# Pointcast_upper_board_V1_03.net
KiCad netlist of a schematic drawn in EAGLE
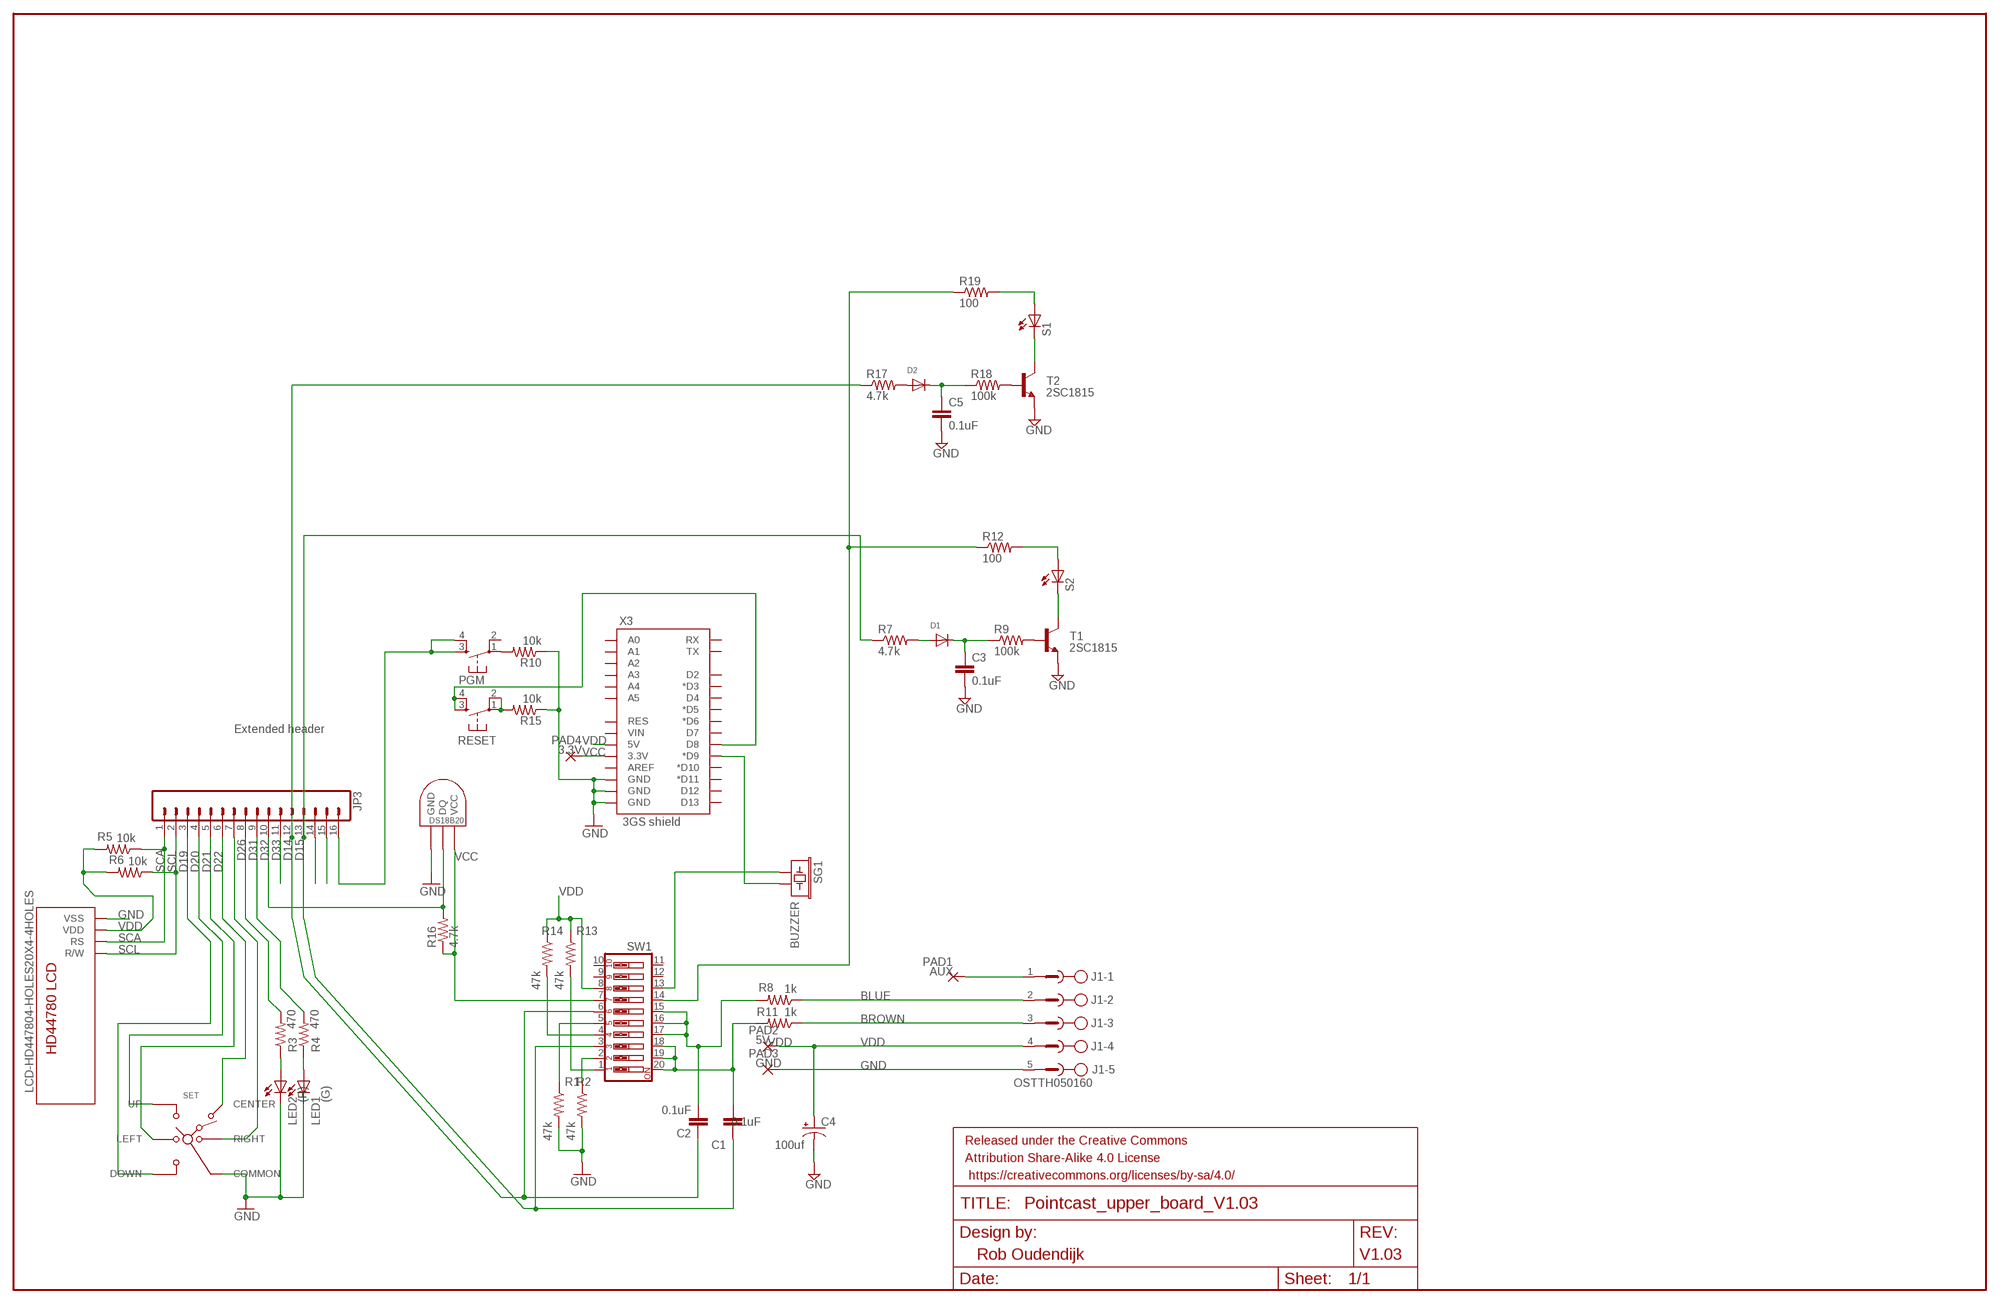
[diagram p0: schematic, sheet 1]

(export (version "E")
  (design (tool "Eeschema 10.0.6"))
  (components
    (comp (ref "C1")
      (value "0.1uF")
      (footprint "eagle-import:C025-024X044")
      (libsource (lib "eagle-import") (part "C-EU025-024X044"))
    )
    (comp (ref "C2")
      (value "0.1uF")
      (footprint "eagle-import:C025-024X044")
      (libsource (lib "eagle-import") (part "C-EU025-024X044"))
    )
    (comp (ref "C3")
      (value "0.1uF")
      (footprint "eagle-import:C025-024X044")
      (libsource (lib "eagle-import") (part "C-EU025-024X044"))
    )
    (comp (ref "C4")
      (value "100uf")
      (footprint "eagle-import:CPOL-RADIAL-100UF-25V")
      (libsource (lib "eagle-import") (part "CAP_POLPTH1"))
    )
    (comp (ref "C5")
      (value "0.1uF")
      (footprint "eagle-import:C025-024X044")
      (libsource (lib "eagle-import") (part "C-EU025-024X044"))
    )
    (comp (ref "D1")
      (value "DIODEDIODE_BIG")
      (footprint "eagle-import:DO41-10")
      (libsource (lib "eagle-import") (part "DIODEDIODE_BIG"))
    )
    (comp (ref "D2")
      (value "DIODEDIODE_BIG")
      (footprint "eagle-import:DO41-10")
      (libsource (lib "eagle-import") (part "DIODEDIODE_BIG"))
    )
    (comp (ref "FRAME1")
      (value "FRAME-LEDGER")
      (footprint "eagle-import:CREATIVE_COMMONS")
      (libsource (lib "eagle-import") (part "FRAME-LEDGER"))
    )
    (comp (ref "J1")
      (value "OSTTH050160")
      (footprint "eagle-import:EDSTL130-05")
      (libsource (lib "eagle-import") (part "OSTTH050160"))
    )
    (comp (ref "JP3")
      (value "Extended header")
      (footprint "eagle-import:1X16")
      (libsource (lib "eagle-import") (part "M16PTH"))
    )
    (comp (ref "LED1")
      (value "(G)")
      (footprint "eagle-import:LED3MM")
      (libsource (lib "eagle-import") (part "LED3MM"))
    )
    (comp (ref "LED2")
      (value "(R)")
      (footprint "eagle-import:LED3MM")
      (libsource (lib "eagle-import") (part "LED3MM"))
    )
    (comp (ref "PAD1")
      (value "AUX")
      (footprint "eagle-import:2,15_1,0")
      (libsource (lib "eagle-import") (part "2,15/1,0"))
    )
    (comp (ref "PAD2")
      (value "5V")
      (footprint "eagle-import:2,15_1,0")
      (libsource (lib "eagle-import") (part "2,15/1,0"))
    )
    (comp (ref "PAD3")
      (value "GND")
      (footprint "eagle-import:2,15_1,0")
      (libsource (lib "eagle-import") (part "2,15/1,0"))
    )
    (comp (ref "PAD4")
      (value "3.3V")
      (footprint "eagle-import:2,15_1,0")
      (libsource (lib "eagle-import") (part "2,15/1,0"))
    )
    (comp (ref "PGM")
      (value "DTS-6")
      (footprint "eagle-import:DTS-6")
      (libsource (lib "eagle-import") (part "DTS-6"))
    )
    (comp (ref "R1")
      (value "47k")
      (footprint "eagle-import:0207_10")
      (libsource (lib "eagle-import") (part "resistor_R-US_0207/10"))
    )
    (comp (ref "R2")
      (value "47k")
      (footprint "eagle-import:0207_10")
      (libsource (lib "eagle-import") (part "resistor_R-US_0207/10"))
    )
    (comp (ref "R3")
      (value "470")
      (footprint "eagle-import:0207_10")
      (libsource (lib "eagle-import") (part "resistor_R-US_0207/10"))
    )
    (comp (ref "R4")
      (value "470")
      (footprint "eagle-import:0207_10")
      (libsource (lib "eagle-import") (part "resistor_R-US_0207/10"))
    )
    (comp (ref "R5")
      (value "10k")
      (footprint "eagle-import:0207_10")
      (libsource (lib "eagle-import") (part "R-US_0207/10"))
    )
    (comp (ref "R6")
      (value "10k")
      (footprint "eagle-import:0207_10")
      (libsource (lib "eagle-import") (part "R-US_0207/10"))
    )
    (comp (ref "R7")
      (value "4.7k")
      (footprint "eagle-import:0207_10")
      (libsource (lib "eagle-import") (part "rcl_R-US_0207/10"))
    )
    (comp (ref "R8")
      (value "1k")
      (footprint "eagle-import:0207_10")
      (libsource (lib "eagle-import") (part "resistor_R-US_0207/10"))
    )
    (comp (ref "R9")
      (value "100k")
      (footprint "eagle-import:0207_10")
      (libsource (lib "eagle-import") (part "rcl_R-US_0207/10"))
    )
    (comp (ref "R10")
      (value "10k")
      (footprint "eagle-import:0207_10")
      (libsource (lib "eagle-import") (part "resistor_R-US_0207/10"))
    )
    (comp (ref "R11")
      (value "1k")
      (footprint "eagle-import:0207_10")
      (libsource (lib "eagle-import") (part "resistor_R-US_0207/10"))
    )
    (comp (ref "R12")
      (value "100")
      (footprint "eagle-import:0207_10")
      (libsource (lib "eagle-import") (part "rcl_R-US_0207/10"))
    )
    (comp (ref "R13")
      (value "47k")
      (footprint "eagle-import:0207_10")
      (libsource (lib "eagle-import") (part "resistor_R-US_0207/10"))
    )
    (comp (ref "R14")
      (value "47k")
      (footprint "eagle-import:0207_10")
      (libsource (lib "eagle-import") (part "resistor_R-US_0207/10"))
    )
    (comp (ref "R15")
      (value "10k")
      (footprint "eagle-import:0207_10")
      (libsource (lib "eagle-import") (part "resistor_R-US_0207/10"))
    )
    (comp (ref "R16")
      (value "4.7k")
      (footprint "eagle-import:0207_10")
      (libsource (lib "eagle-import") (part "resistor_R-US_0207/10"))
    )
    (comp (ref "R17")
      (value "4.7k")
      (footprint "eagle-import:0207_10")
      (libsource (lib "eagle-import") (part "rcl_R-US_0207/10"))
    )
    (comp (ref "R18")
      (value "100k")
      (footprint "eagle-import:0207_10")
      (libsource (lib "eagle-import") (part "rcl_R-US_0207/10"))
    )
    (comp (ref "R19")
      (value "100")
      (footprint "eagle-import:0207_10")
      (libsource (lib "eagle-import") (part "rcl_R-US_0207/10"))
    )
    (comp (ref "RESET")
      (value "DTS-6")
      (footprint "eagle-import:DTS-6")
      (libsource (lib "eagle-import") (part "DTS-6"))
    )
    (comp (ref "S1")
      (value "LED3MM")
      (footprint "eagle-import:LED3MM")
      (libsource (lib "eagle-import") (part "LED3MM"))
    )
    (comp (ref "S2")
      (value "LED3MM")
      (footprint "eagle-import:LED3MM")
      (libsource (lib "eagle-import") (part "LED3MM"))
    )
    (comp (ref "SET")
      (value "SKQUCAA010")
      (footprint "eagle-import:SKQU")
      (fields (field (name "MF") "ALPS"))
      (libsource (lib "eagle-import") (part "SKQUCAA010"))
    )
    (comp (ref "SG1")
      (value "BUZZER")
      (footprint "eagle-import:BUZZER-12MM")
      (libsource (lib "eagle-import") (part "BUZZERPTH"))
    )
    (comp (ref "SW1")
      (value "SW_DIP-10")
      (footprint "eagle-import:EDG-10")
      (libsource (lib "eagle-import") (part "SW_DIP-10"))
    )
    (comp (ref "T1")
      (value "2SC1815")
      (footprint "eagle-import:TO92-ECB")
      (libsource (lib "eagle-import") (part "2SC1815"))
    )
    (comp (ref "T2")
      (value "2SC1815")
      (footprint "eagle-import:TO92-ECB")
      (libsource (lib "eagle-import") (part "2SC1815"))
    )
    (comp (ref "TEMP")
      (value "AVA_DS1820TO92")
      (footprint "eagle-import:AVA_DS1820")
      (libsource (lib "eagle-import") (part "AVA_DS1820TO92"))
    )
    (comp (ref "X1")
      (value "LCD-HD447804-HOLES20X4-4HOLES")
      (footprint "eagle-import:LCD-20X4-4HOLES")
      (libsource (lib "eagle-import") (part "LCD-HD4478020X4-4HOLES4-HOLES"))
    )
    (comp (ref "X3")
      (value "3GS shield")
      (footprint "eagle-import:DUEMILANOVE_SHIELD")
      (libsource (lib "eagle-import") (part "ARDUINO_SHIELDLABEL"))
    )
  )
  (nets
    (net (code "1") (name "/BLUE") (class "Default")
      (node (ref "J1") (pin "2") (pinfunction "SK_2") (pintype "passive"))
      (node (ref "R8") (pin "1") (pinfunction "1_1") (pintype "passive"))
    )
    (net (code "2") (name "/BROWN") (class "Default")
      (node (ref "J1") (pin "3") (pinfunction "SK_3") (pintype "passive"))
      (node (ref "R11") (pin "1") (pinfunction "1_1") (pintype "passive"))
    )
    (net (code "3") (name "/D14") (class "Default")
      (node (ref "C2") (pin "1") (pinfunction "1_1") (pintype "passive"))
      (node (ref "JP3") (pin "12") (pinfunction "12_12") (pintype "passive"))
      (node (ref "R17") (pin "1") (pinfunction "1_1") (pintype "passive"))
      (node (ref "SW1") (pin "6") (pinfunction "6_6") (pintype "passive"))
    )
    (net (code "4") (name "/D15") (class "Default")
      (node (ref "C1") (pin "1") (pinfunction "1_1") (pintype "passive"))
      (node (ref "JP3") (pin "13") (pinfunction "13_13") (pintype "passive"))
      (node (ref "R7") (pin "1") (pinfunction "1_1") (pintype "passive"))
      (node (ref "SW1") (pin "3") (pinfunction "3_3") (pintype "passive"))
    )
    (net (code "5") (name "/D19") (class "Default")
      (node (ref "JP3") (pin "3") (pinfunction "3_3") (pintype "passive"))
      (node (ref "SET") (pin "DOWN") (pinfunction "DOWN_DOWN") (pintype "passive"))
    )
    (net (code "6") (name "/D20") (class "Default")
      (node (ref "JP3") (pin "4") (pinfunction "4_4") (pintype "passive"))
      (node (ref "SET") (pin "UP") (pinfunction "UP_UP") (pintype "passive"))
    )
    (net (code "7") (name "/D21") (class "Default")
      (node (ref "JP3") (pin "5") (pinfunction "5_5") (pintype "passive"))
      (node (ref "SET") (pin "LEFT") (pinfunction "LEFT_LEFT") (pintype "passive"))
    )
    (net (code "8") (name "/D22") (class "Default")
      (node (ref "JP3") (pin "6") (pinfunction "6_6") (pintype "passive"))
      (node (ref "SET") (pin "CENTER") (pinfunction "CENTER_CENTER") (pintype "passive"))
    )
    (net (code "9") (name "/D26") (class "Default")
      (node (ref "JP3") (pin "8") (pinfunction "8_8") (pintype "passive"))
      (node (ref "R3") (pin "2") (pinfunction "2_2") (pintype "passive"))
    )
    (net (code "10") (name "/D31") (class "Default")
      (node (ref "JP3") (pin "9") (pinfunction "9_9") (pintype "passive"))
      (node (ref "R4") (pin "2") (pinfunction "2_2") (pintype "passive"))
    )
    (net (code "11") (name "/D32") (class "Default")
      (node (ref "JP3") (pin "10") (pinfunction "10_10") (pintype "passive"))
      (node (ref "R16") (pin "2") (pinfunction "2_2") (pintype "passive"))
      (node (ref "TEMP") (pin "DQ") (pinfunction "DQ_DQ") (pintype "bidirectional"))
    )
    (net (code "12") (name "/D33") (class "Default")
      (node (ref "JP3") (pin "11") (pinfunction "11_11") (pintype "passive"))
    )
    (net (code "13") (name "/SCA") (class "Default")
      (node (ref "JP3") (pin "1") (pinfunction "1_1") (pintype "passive"))
      (node (ref "R5") (pin "1") (pinfunction "1_1") (pintype "passive"))
      (node (ref "X1") (pin "P$15") (pinfunction "RS_P$15") (pintype "input"))
    )
    (net (code "14") (name "/SCL") (class "Default")
      (node (ref "JP3") (pin "2") (pinfunction "2_2") (pintype "passive"))
      (node (ref "R6") (pin "1") (pinfunction "1_1") (pintype "passive"))
      (node (ref "X1") (pin "P$16") (pinfunction "R/W_P$16") (pintype "input"))
    )
    (net (code "15") (name "/VCC") (class "Default")
      (node (ref "PAD4") (pin "1") (pinfunction "P_1") (pintype "passive"))
      (node (ref "R16") (pin "1") (pinfunction "1_1") (pintype "passive"))
      (node (ref "SW1") (pin "7") (pinfunction "7_7") (pintype "passive"))
      (node (ref "TEMP") (pin "VDD") (pinfunction "VCC_VDD") (pintype "power_in"))
      (node (ref "X3") (pin "3.3V") (pinfunction "3.3V_3.3V") (pintype "bidirectional"))
    )
    (net (code "16") (name "/VDD") (class "Default")
      (node (ref "C4") (pin "2") (pinfunction "+_2") (pintype "passive"))
      (node (ref "J1") (pin "4") (pinfunction "SK_4") (pintype "passive"))
      (node (ref "PAD2") (pin "1") (pinfunction "P_1") (pintype "passive"))
      (node (ref "R13") (pin "1") (pinfunction "1_1") (pintype "passive"))
      (node (ref "R14") (pin "1") (pinfunction "1_1") (pintype "passive"))
      (node (ref "R5") (pin "2") (pinfunction "2_2") (pintype "passive"))
      (node (ref "R6") (pin "2") (pinfunction "2_2") (pintype "passive"))
      (node (ref "SW1") (pin "8") (pinfunction "8_8") (pintype "passive"))
      (node (ref "X1") (pin "P$14") (pinfunction "VDD_P$14") (pintype "power_in"))
      (node (ref "X3") (pin "5V") (pinfunction "5V_5V") (pintype "bidirectional"))
    )
    (net (code "17") (name "GND") (class "Default")
      (node (ref "C3") (pin "2") (pinfunction "2_2") (pintype "passive"))
      (node (ref "C4") (pin "1") (pinfunction "-_1") (pintype "passive"))
      (node (ref "C5") (pin "2") (pinfunction "2_2") (pintype "passive"))
      (node (ref "J1") (pin "5") (pinfunction "SK_5") (pintype "passive"))
      (node (ref "LED1") (pin "K") (pinfunction "C_K") (pintype "passive"))
      (node (ref "LED2") (pin "K") (pinfunction "C_K") (pintype "passive"))
      (node (ref "PAD3") (pin "1") (pinfunction "P_1") (pintype "passive"))
      (node (ref "R1") (pin "2") (pinfunction "2_2") (pintype "passive"))
      (node (ref "R10") (pin "1") (pinfunction "1_1") (pintype "passive"))
      (node (ref "R15") (pin "1") (pinfunction "1_1") (pintype "passive"))
      (node (ref "R2") (pin "2") (pinfunction "2_2") (pintype "passive"))
      (node (ref "SET") (pin "COMMON") (pinfunction "COMMON_COMMON") (pintype "power_in"))
      (node (ref "T1") (pin "E") (pinfunction "E_E") (pintype "passive"))
      (node (ref "T2") (pin "E") (pinfunction "E_E") (pintype "passive"))
      (node (ref "TEMP") (pin "GND") (pinfunction "GND_GND") (pintype "power_in"))
      (node (ref "X1") (pin "P$13") (pinfunction "VSS_P$13") (pintype "power_in"))
      (node (ref "X3") (pin "GND@0") (pinfunction "GND_GND@0") (pintype "bidirectional"))
      (node (ref "X3") (pin "GND@1") (pinfunction "GND_GND@1") (pintype "bidirectional"))
      (node (ref "X3") (pin "GND@2") (pinfunction "GND_GND@2") (pintype "bidirectional"))
    )
    (net (code "18") (name "Net-(C1-Pad2)") (class "Default")
      (node (ref "C1") (pin "2") (pinfunction "2_2") (pintype "passive"))
      (node (ref "R11") (pin "2") (pinfunction "2_2") (pintype "passive"))
      (node (ref "SW1") (pin "18") (pinfunction "18_18") (pintype "passive"))
      (node (ref "SW1") (pin "19") (pinfunction "19_19") (pintype "passive"))
      (node (ref "SW1") (pin "20") (pinfunction "20_20") (pintype "passive"))
    )
    (net (code "19") (name "Net-(C2-Pad2)") (class "Default")
      (node (ref "C2") (pin "2") (pinfunction "2_2") (pintype "passive"))
      (node (ref "R8") (pin "2") (pinfunction "2_2") (pintype "passive"))
      (node (ref "SW1") (pin "15") (pinfunction "15_15") (pintype "passive"))
      (node (ref "SW1") (pin "16") (pinfunction "16_16") (pintype "passive"))
      (node (ref "SW1") (pin "17") (pinfunction "17_17") (pintype "passive"))
    )
    (net (code "20") (name "Net-(C3-Pad1)") (class "Default")
      (node (ref "C3") (pin "1") (pinfunction "1_1") (pintype "passive"))
      (node (ref "D1") (pin "C") (pinfunction "C_C") (pintype "passive"))
      (node (ref "R9") (pin "1") (pinfunction "1_1") (pintype "passive"))
    )
    (net (code "21") (name "Net-(C5-Pad1)") (class "Default")
      (node (ref "C5") (pin "1") (pinfunction "1_1") (pintype "passive"))
      (node (ref "D2") (pin "C") (pinfunction "C_C") (pintype "passive"))
      (node (ref "R18") (pin "1") (pinfunction "1_1") (pintype "passive"))
    )
    (net (code "22") (name "Net-(D1-PadA)") (class "Default")
      (node (ref "D1") (pin "A") (pinfunction "A_A") (pintype "passive"))
      (node (ref "R7") (pin "2") (pinfunction "2_2") (pintype "passive"))
    )
    (net (code "23") (name "Net-(D2-PadA)") (class "Default")
      (node (ref "D2") (pin "A") (pinfunction "A_A") (pintype "passive"))
      (node (ref "R17") (pin "2") (pinfunction "2_2") (pintype "passive"))
    )
    (net (code "24") (name "Net-(J1A-SK)") (class "Default")
      (node (ref "J1") (pin "1") (pinfunction "SK_1") (pintype "passive"))
      (node (ref "PAD1") (pin "1") (pinfunction "P_1") (pintype "passive"))
    )
    (net (code "25") (name "Net-(JP3-Pad7)") (class "Default")
      (node (ref "JP3") (pin "7") (pinfunction "7_7") (pintype "passive"))
      (node (ref "SET") (pin "RIGHT") (pinfunction "RIGHT_RIGHT") (pintype "passive"))
    )
    (net (code "26") (name "Net-(JP3-Pad16)") (class "Default")
      (node (ref "JP3") (pin "16") (pinfunction "16_16") (pintype "passive"))
      (node (ref "PGM") (pin "3") (pinfunction "3_3") (pintype "passive"))
      (node (ref "PGM") (pin "4") (pinfunction "4_4") (pintype "passive"))
    )
    (net (code "27") (name "Net-(LED1-PadA)") (class "Default")
      (node (ref "LED1") (pin "A") (pinfunction "A_A") (pintype "passive"))
      (node (ref "R4") (pin "1") (pinfunction "1_1") (pintype "passive"))
    )
    (net (code "28") (name "Net-(LED2-PadA)") (class "Default")
      (node (ref "LED2") (pin "A") (pinfunction "A_A") (pintype "passive"))
      (node (ref "R3") (pin "1") (pinfunction "1_1") (pintype "passive"))
    )
    (net (code "29") (name "Net-(PGM-Pad1)") (class "Default")
      (node (ref "PGM") (pin "1") (pinfunction "1_1") (pintype "passive"))
      (node (ref "R10") (pin "2") (pinfunction "2_2") (pintype "passive"))
    )
    (net (code "30") (name "Net-(R1-Pad1)") (class "Default")
      (node (ref "R1") (pin "1") (pinfunction "1_1") (pintype "passive"))
      (node (ref "SW1") (pin "5") (pinfunction "5_5") (pintype "passive"))
    )
    (net (code "31") (name "Net-(R2-Pad1)") (class "Default")
      (node (ref "R2") (pin "1") (pinfunction "1_1") (pintype "passive"))
      (node (ref "SW1") (pin "2") (pinfunction "2_2") (pintype "passive"))
    )
    (net (code "32") (name "Net-(R9-Pad2)") (class "Default")
      (node (ref "R9") (pin "2") (pinfunction "2_2") (pintype "passive"))
      (node (ref "T1") (pin "B") (pinfunction "B_B") (pintype "passive"))
    )
    (net (code "33") (name "Net-(R12-Pad1)") (class "Default")
      (node (ref "R12") (pin "1") (pinfunction "1_1") (pintype "passive"))
      (node (ref "R19") (pin "1") (pinfunction "1_1") (pintype "passive"))
      (node (ref "SW1") (pin "14") (pinfunction "14_14") (pintype "passive"))
    )
    (net (code "34") (name "Net-(R12-Pad2)") (class "Default")
      (node (ref "R12") (pin "2") (pinfunction "2_2") (pintype "passive"))
      (node (ref "S2") (pin "A") (pinfunction "A_A") (pintype "passive"))
    )
    (net (code "35") (name "Net-(R13-Pad2)") (class "Default")
      (node (ref "R13") (pin "2") (pinfunction "2_2") (pintype "passive"))
      (node (ref "SW1") (pin "1") (pinfunction "1_1") (pintype "passive"))
    )
    (net (code "36") (name "Net-(R14-Pad2)") (class "Default")
      (node (ref "R14") (pin "2") (pinfunction "2_2") (pintype "passive"))
      (node (ref "SW1") (pin "4") (pinfunction "4_4") (pintype "passive"))
    )
    (net (code "37") (name "Net-(R15-Pad2)") (class "Default")
      (node (ref "R15") (pin "2") (pinfunction "2_2") (pintype "passive"))
      (node (ref "RESET") (pin "1") (pinfunction "1_1") (pintype "passive"))
      (node (ref "RESET") (pin "2") (pinfunction "2_2") (pintype "passive"))
    )
    (net (code "38") (name "Net-(R18-Pad2)") (class "Default")
      (node (ref "R18") (pin "2") (pinfunction "2_2") (pintype "passive"))
      (node (ref "T2") (pin "B") (pinfunction "B_B") (pintype "passive"))
    )
    (net (code "39") (name "Net-(R19-Pad2)") (class "Default")
      (node (ref "R19") (pin "2") (pinfunction "2_2") (pintype "passive"))
      (node (ref "S1") (pin "A") (pinfunction "A_A") (pintype "passive"))
    )
    (net (code "40") (name "Net-(RESET-Pad3)") (class "Default")
      (node (ref "RESET") (pin "3") (pinfunction "3_3") (pintype "passive"))
      (node (ref "RESET") (pin "4") (pinfunction "4_4") (pintype "passive"))
      (node (ref "X3") (pin "D8") (pinfunction "D8_D8") (pintype "bidirectional"))
    )
    (net (code "41") (name "Net-(S1-C)") (class "Default")
      (node (ref "S1") (pin "K") (pinfunction "C_K") (pintype "passive"))
      (node (ref "T2") (pin "C") (pinfunction "C_C") (pintype "passive"))
    )
    (net (code "42") (name "Net-(S2-C)") (class "Default")
      (node (ref "S2") (pin "K") (pinfunction "C_K") (pintype "passive"))
      (node (ref "T1") (pin "C") (pinfunction "C_C") (pintype "passive"))
    )
    (net (code "43") (name "Net-(SG1-1)") (class "Default")
      (node (ref "SG1") (pin "+") (pinfunction "1_+") (pintype "passive"))
      (node (ref "SW1") (pin "13") (pinfunction "13_13") (pintype "passive"))
    )
    (net (code "44") (name "Net-(SG1-2)") (class "Default")
      (node (ref "SG1") (pin "-") (pinfunction "2_-") (pintype "passive"))
      (node (ref "X3") (pin "D9") (pinfunction "*D9_D9") (pintype "bidirectional"))
    )
    (net (code "45") (name "unconnected-(JP3-Pad14)") (class "Default")
      (node (ref "JP3") (pin "14") (pinfunction "14_14") (pintype "passive"))
    )
    (net (code "46") (name "unconnected-(JP3-Pad15)") (class "Default")
      (node (ref "JP3") (pin "15") (pinfunction "15_15") (pintype "passive"))
    )
    (net (code "47") (name "unconnected-(PGM-Pad2)") (class "Default")
      (node (ref "PGM") (pin "2") (pinfunction "2_2") (pintype "passive"))
    )
    (net (code "48") (name "unconnected-(SW1-Pad9)") (class "Default")
      (node (ref "SW1") (pin "9") (pinfunction "9_9") (pintype "passive"))
    )
    (net (code "49") (name "unconnected-(SW1-Pad10)") (class "Default")
      (node (ref "SW1") (pin "10") (pinfunction "10_10") (pintype "passive"))
    )
    (net (code "50") (name "unconnected-(SW1-Pad11)") (class "Default")
      (node (ref "SW1") (pin "11") (pinfunction "11_11") (pintype "passive"))
    )
    (net (code "51") (name "unconnected-(SW1-Pad12)") (class "Default")
      (node (ref "SW1") (pin "12") (pinfunction "12_12") (pintype "passive"))
    )
    (net (code "52") (name "unconnected-(X3-*D3-PadD3)") (class "Default")
      (node (ref "X3") (pin "D3") (pinfunction "*D3_D3") (pintype "bidirectional"))
    )
    (net (code "53") (name "unconnected-(X3-*D5-PadD5)") (class "Default")
      (node (ref "X3") (pin "D5") (pinfunction "*D5_D5") (pintype "bidirectional"))
    )
    (net (code "54") (name "unconnected-(X3-*D6-PadD6)") (class "Default")
      (node (ref "X3") (pin "D6") (pinfunction "*D6_D6") (pintype "bidirectional"))
    )
    (net (code "55") (name "unconnected-(X3-*D10-PadD10)") (class "Default")
      (node (ref "X3") (pin "D10") (pinfunction "*D10_D10") (pintype "bidirectional"))
    )
    (net (code "56") (name "unconnected-(X3-*D11-PadD11)") (class "Default")
      (node (ref "X3") (pin "D11") (pinfunction "*D11_D11") (pintype "bidirectional"))
    )
    (net (code "57") (name "unconnected-(X3-PadA0)") (class "Default")
      (node (ref "X3") (pin "A0") (pinfunction "A0_A0") (pintype "bidirectional"))
    )
    (net (code "58") (name "unconnected-(X3-PadA1)") (class "Default")
      (node (ref "X3") (pin "A1") (pinfunction "A1_A1") (pintype "bidirectional"))
    )
    (net (code "59") (name "unconnected-(X3-PadA2)") (class "Default")
      (node (ref "X3") (pin "A2") (pinfunction "A2_A2") (pintype "bidirectional"))
    )
    (net (code "60") (name "unconnected-(X3-PadA3)") (class "Default")
      (node (ref "X3") (pin "A3") (pinfunction "A3_A3") (pintype "bidirectional"))
    )
    (net (code "61") (name "unconnected-(X3-PadA4)") (class "Default")
      (node (ref "X3") (pin "A4") (pinfunction "A4_A4") (pintype "bidirectional"))
    )
    (net (code "62") (name "unconnected-(X3-PadA5)") (class "Default")
      (node (ref "X3") (pin "A5") (pinfunction "A5_A5") (pintype "bidirectional"))
    )
    (net (code "63") (name "unconnected-(X3-PadAREF)") (class "Default")
      (node (ref "X3") (pin "AREF") (pinfunction "AREF_AREF") (pintype "bidirectional"))
    )
    (net (code "64") (name "unconnected-(X3-PadD2)") (class "Default")
      (node (ref "X3") (pin "D2") (pinfunction "D2_D2") (pintype "bidirectional"))
    )
    (net (code "65") (name "unconnected-(X3-PadD4)") (class "Default")
      (node (ref "X3") (pin "D4") (pinfunction "D4_D4") (pintype "bidirectional"))
    )
    (net (code "66") (name "unconnected-(X3-PadD7)") (class "Default")
      (node (ref "X3") (pin "D7") (pinfunction "D7_D7") (pintype "bidirectional"))
    )
    (net (code "67") (name "unconnected-(X3-PadD12)") (class "Default")
      (node (ref "X3") (pin "D12") (pinfunction "D12_D12") (pintype "bidirectional"))
    )
    (net (code "68") (name "unconnected-(X3-PadD13)") (class "Default")
      (node (ref "X3") (pin "D13") (pinfunction "D13_D13") (pintype "bidirectional"))
    )
    (net (code "69") (name "unconnected-(X3-PadRES)") (class "Default")
      (node (ref "X3") (pin "RES") (pinfunction "RES_RES") (pintype "bidirectional"))
    )
    (net (code "70") (name "unconnected-(X3-PadRX)") (class "Default")
      (node (ref "X3") (pin "RX") (pinfunction "RX_RX") (pintype "bidirectional"))
    )
    (net (code "71") (name "unconnected-(X3-PadTX)") (class "Default")
      (node (ref "X3") (pin "TX") (pinfunction "TX_TX") (pintype "bidirectional"))
    )
    (net (code "72") (name "unconnected-(X3-PadVIN)") (class "Default")
      (node (ref "X3") (pin "VIN") (pinfunction "VIN_VIN") (pintype "bidirectional"))
    )
  )
)
